# eled01.net
KiCad netlist of a schematic drawn in EAGLE
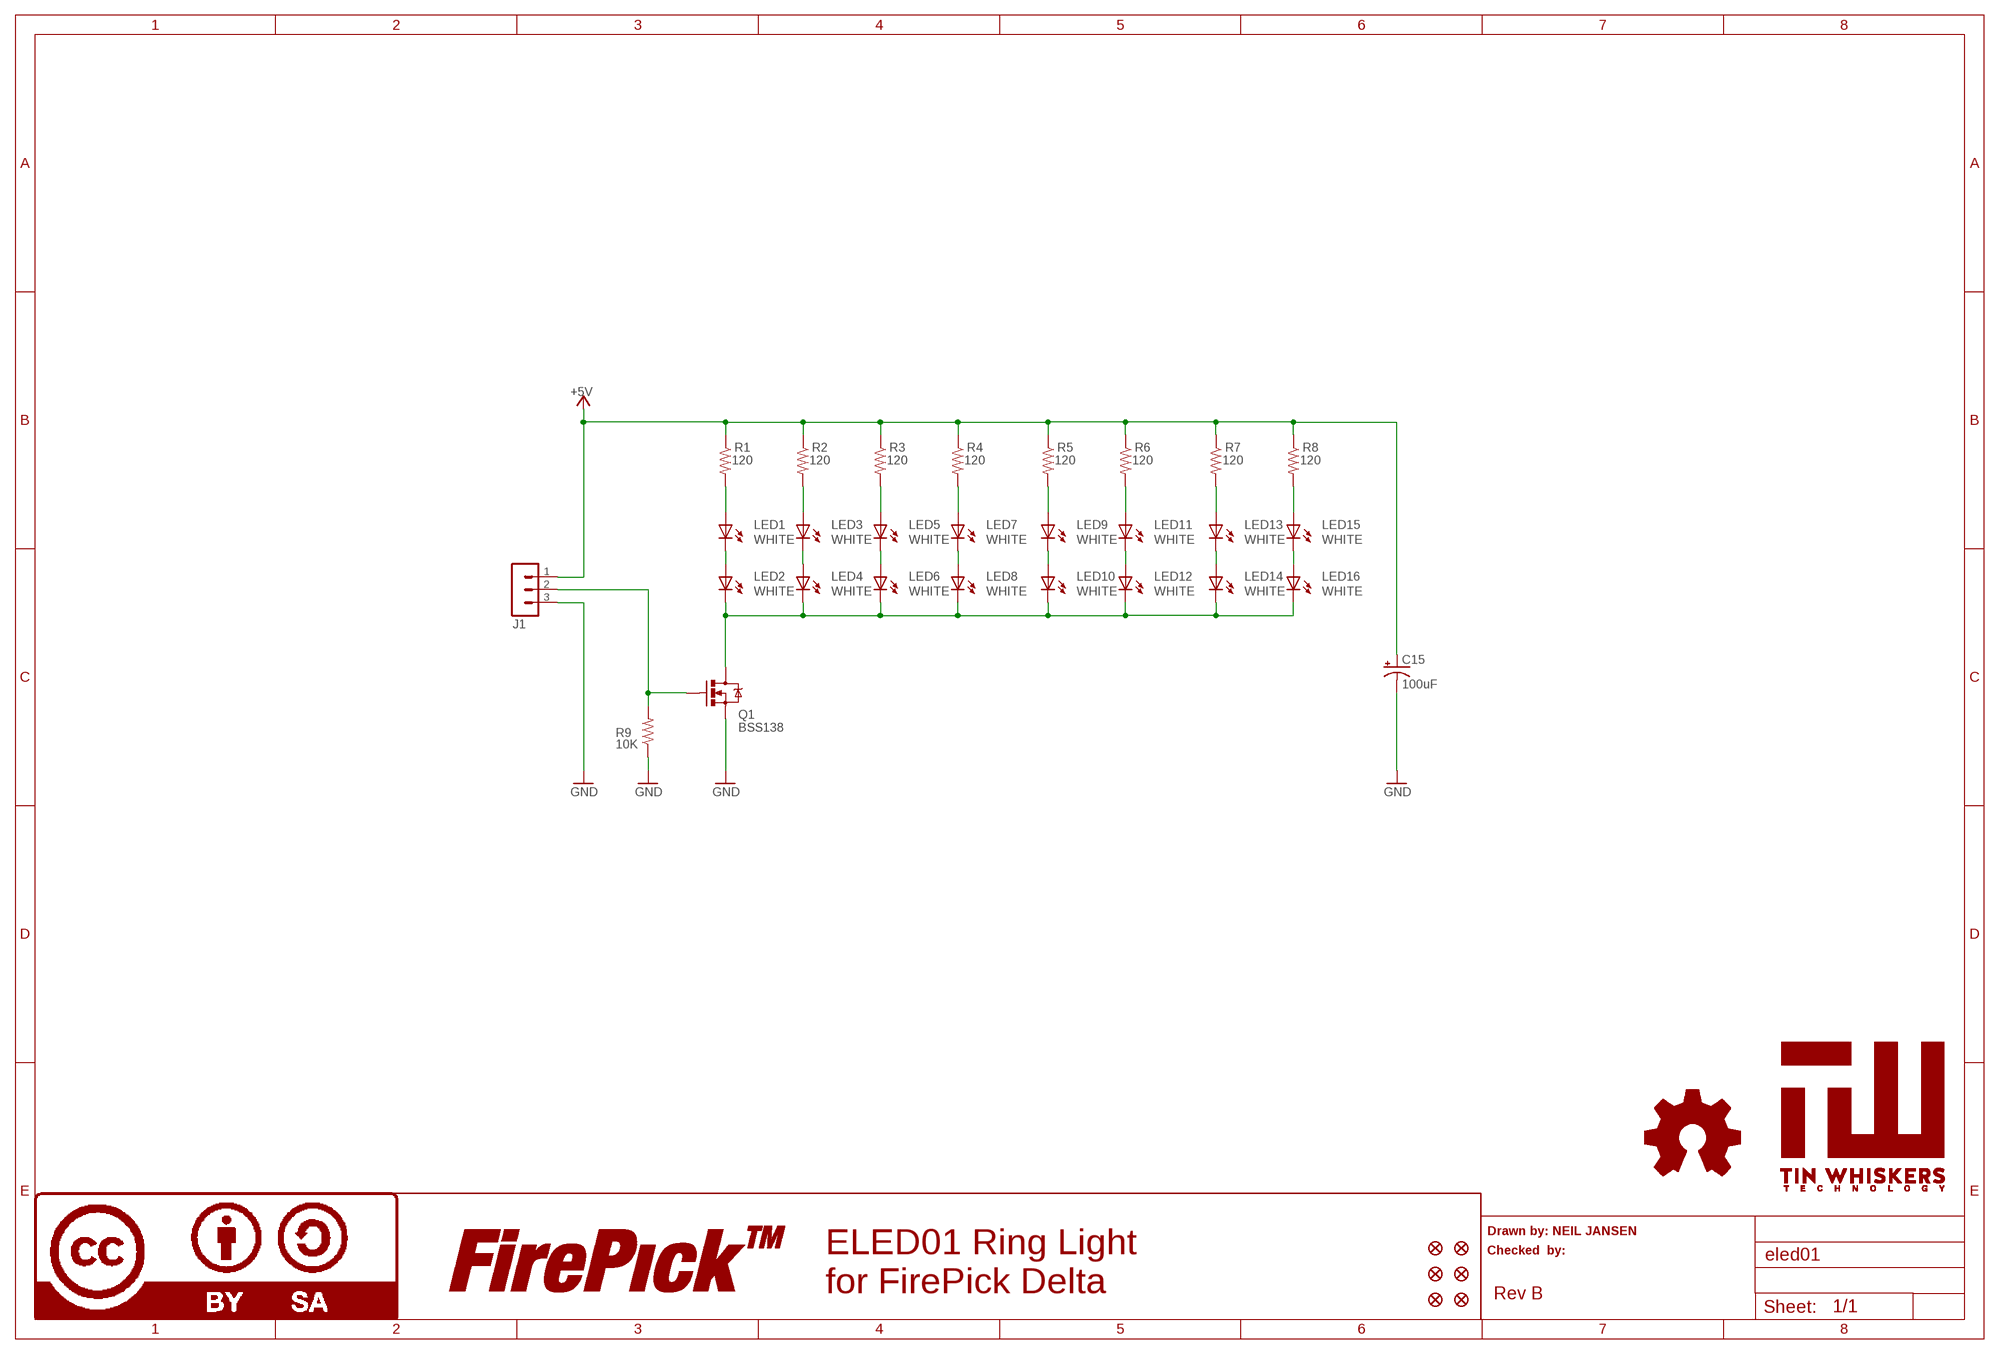
[diagram p0: schematic, sheet 1]

(export (version "E")
  (design (tool "Eeschema 10.0.6"))
  (components
    (comp (ref "C15")
      (value "100uF")
      (footprint "eagle-import:PANASONIC_D")
      (fields (field (name "PARTNO") "25TXV100M6.3X8"))
      (libsource (lib "eagle-import") (part "CPOL-USD"))
    )
    (comp (ref "FID1")
      (value "FIDUCIAL")
      (footprint "eagle-import:FIDUCIAL")
      (libsource (lib "eagle-import") (part "FIDUCIAL"))
    )
    (comp (ref "FID2")
      (value "FIDUCIAL")
      (footprint "eagle-import:FIDUCIAL")
      (libsource (lib "eagle-import") (part "FIDUCIAL"))
    )
    (comp (ref "FID3")
      (value "FIDUCIAL")
      (footprint "eagle-import:FIDUCIAL")
      (libsource (lib "eagle-import") (part "FIDUCIAL"))
    )
    (comp (ref "FID4")
      (value "FIDUCIAL")
      (footprint "eagle-import:FIDUCIAL")
      (libsource (lib "eagle-import") (part "FIDUCIAL"))
    )
    (comp (ref "FID5")
      (value "FIDUCIAL")
      (footprint "eagle-import:FIDUCIAL")
      (libsource (lib "eagle-import") (part "FIDUCIAL"))
    )
    (comp (ref "FID6")
      (value "FIDUCIAL")
      (footprint "eagle-import:FIDUCIAL")
      (libsource (lib "eagle-import") (part "FIDUCIAL"))
    )
    (comp (ref "J1")
      (value "MA03-1")
      (footprint "eagle-import:MA03-1")
      (fields (field (name "PARTNO") "CONN-0.1-RA-1X3"))
      (libsource (lib "eagle-import") (part "MA03-1"))
    )
    (comp (ref "LED1")
      (value "WHITE")
      (footprint "eagle-import:LED-1206-NO_SILK")
      (fields (field (name "PARTNO") "LTST-C150CKT"))
      (libsource (lib "eagle-import") (part "LED1206-NS"))
    )
    (comp (ref "LED2")
      (value "WHITE")
      (footprint "eagle-import:LED-1206-NO_SILK")
      (fields (field (name "PARTNO") "LTST-C150CKT"))
      (libsource (lib "eagle-import") (part "LED1206-NS"))
    )
    (comp (ref "LED3")
      (value "WHITE")
      (footprint "eagle-import:LED-1206-NO_SILK")
      (fields (field (name "PARTNO") "LTST-C150CKT"))
      (libsource (lib "eagle-import") (part "LED1206-NS"))
    )
    (comp (ref "LED4")
      (value "WHITE")
      (footprint "eagle-import:LED-1206-NO_SILK")
      (fields (field (name "PARTNO") "LTST-C150CKT"))
      (libsource (lib "eagle-import") (part "LED1206-NS"))
    )
    (comp (ref "LED5")
      (value "WHITE")
      (footprint "eagle-import:LED-1206-NO_SILK")
      (fields (field (name "PARTNO") "LTST-C150CKT"))
      (libsource (lib "eagle-import") (part "LED1206-NS"))
    )
    (comp (ref "LED6")
      (value "WHITE")
      (footprint "eagle-import:LED-1206-NO_SILK")
      (fields (field (name "PARTNO") "LTST-C150CKT"))
      (libsource (lib "eagle-import") (part "LED1206-NS"))
    )
    (comp (ref "LED7")
      (value "WHITE")
      (footprint "eagle-import:LED-1206-NO_SILK")
      (fields (field (name "PARTNO") "LTST-C150CKT"))
      (libsource (lib "eagle-import") (part "LED1206-NS"))
    )
    (comp (ref "LED8")
      (value "WHITE")
      (footprint "eagle-import:LED-1206-NO_SILK")
      (fields (field (name "PARTNO") "LTST-C150CKT"))
      (libsource (lib "eagle-import") (part "LED1206-NS"))
    )
    (comp (ref "LED9")
      (value "WHITE")
      (footprint "eagle-import:LED-1206-NO_SILK")
      (fields (field (name "PARTNO") "LTST-C150CKT"))
      (libsource (lib "eagle-import") (part "LED1206-NS"))
    )
    (comp (ref "LED10")
      (value "WHITE")
      (footprint "eagle-import:LED-1206-NO_SILK")
      (fields (field (name "PARTNO") "LTST-C150CKT"))
      (libsource (lib "eagle-import") (part "LED1206-NS"))
    )
    (comp (ref "LED11")
      (value "WHITE")
      (footprint "eagle-import:LED-1206-NO_SILK")
      (fields (field (name "PARTNO") "LTST-C150CKT"))
      (libsource (lib "eagle-import") (part "LED1206-NS"))
    )
    (comp (ref "LED12")
      (value "WHITE")
      (footprint "eagle-import:LED-1206-NO_SILK")
      (fields (field (name "PARTNO") "LTST-C150CKT"))
      (libsource (lib "eagle-import") (part "LED1206-NS"))
    )
    (comp (ref "LED13")
      (value "WHITE")
      (footprint "eagle-import:LED-1206-NO_SILK")
      (fields (field (name "PARTNO") "LTST-C150CKT"))
      (libsource (lib "eagle-import") (part "LED1206-NS"))
    )
    (comp (ref "LED14")
      (value "WHITE")
      (footprint "eagle-import:LED-1206-NO_SILK")
      (fields (field (name "PARTNO") "LTST-C150CKT"))
      (libsource (lib "eagle-import") (part "LED1206-NS"))
    )
    (comp (ref "LED15")
      (value "WHITE")
      (footprint "eagle-import:LED-1206-NO_SILK")
      (fields (field (name "PARTNO") "LTST-C150CKT"))
      (libsource (lib "eagle-import") (part "LED1206-NS"))
    )
    (comp (ref "LED16")
      (value "WHITE")
      (footprint "eagle-import:LED-1206-NO_SILK")
      (fields (field (name "PARTNO") "LTST-C150CKT"))
      (libsource (lib "eagle-import") (part "LED1206-NS"))
    )
    (comp (ref "LOGO2")
      (value "LOGO-OSHWSMALL")
      (footprint "eagle-import:LOGO-OSHW-SMALL")
      (libsource (lib "eagle-import") (part "LOGO-OSHWSMALL"))
    )
    (comp (ref "LOGO4")
      (value "LOGO-FIREPICKMEDIUM")
      (footprint "eagle-import:LOGO-FIREPICK-MEDIUM")
      (libsource (lib "eagle-import") (part "LOGO-FIREPICKMEDIUM"))
    )
    (comp (ref "LOGO6")
      (value "LOGO-CC-BY-SAMEDIUM")
      (footprint "eagle-import:LOGO-CC-BY-SA-MEDIUM")
      (libsource (lib "eagle-import") (part "LOGO-CC-BY-SAMEDIUM"))
    )
    (comp (ref "Q1")
      (value "BSS138")
      (footprint "eagle-import:SOT23")
      (libsource (lib "eagle-import") (part "MOSFET-NCHANNELBSS138"))
    )
    (comp (ref "R1")
      (value "120")
      (footprint "eagle-import:0805")
      (fields (field (name "PARTNO") "RC0805FR-07120RL"))
      (libsource (lib "eagle-import") (part "RESISTOR0805-RES"))
    )
    (comp (ref "R2")
      (value "120")
      (footprint "eagle-import:0805")
      (fields (field (name "PARTNO") "RC0805FR-07120RL"))
      (libsource (lib "eagle-import") (part "RESISTOR0805-RES"))
    )
    (comp (ref "R3")
      (value "120")
      (footprint "eagle-import:0805")
      (fields (field (name "PARTNO") "RC0805FR-07120RL"))
      (libsource (lib "eagle-import") (part "RESISTOR0805-RES"))
    )
    (comp (ref "R4")
      (value "120")
      (footprint "eagle-import:0805")
      (fields (field (name "PARTNO") "RC0805FR-07120RL"))
      (libsource (lib "eagle-import") (part "RESISTOR0805-RES"))
    )
    (comp (ref "R5")
      (value "120")
      (footprint "eagle-import:0805")
      (fields (field (name "PARTNO") "RC0805FR-07120RL"))
      (libsource (lib "eagle-import") (part "RESISTOR0805-RES"))
    )
    (comp (ref "R6")
      (value "120")
      (footprint "eagle-import:0805")
      (fields (field (name "PARTNO") "RC0805FR-07120RL"))
      (libsource (lib "eagle-import") (part "RESISTOR0805-RES"))
    )
    (comp (ref "R7")
      (value "120")
      (footprint "eagle-import:0805")
      (fields (field (name "PARTNO") "RC0805FR-07120RL"))
      (libsource (lib "eagle-import") (part "RESISTOR0805-RES"))
    )
    (comp (ref "R8")
      (value "120")
      (footprint "eagle-import:0805")
      (fields (field (name "PARTNO") "RC0805FR-07120RL"))
      (libsource (lib "eagle-import") (part "RESISTOR0805-RES"))
    )
    (comp (ref "R9")
      (value "10K")
      (footprint "eagle-import:0805")
      (fields (field (name "PARTNO") "RC0805FR-0710KL"))
      (libsource (lib "eagle-import") (part "RESISTOR0805-RES"))
    )
    (comp (ref "U$1")
      (value "TIN-WHISKERSSMALL")
      (footprint "eagle-import:TIN-WHISKERS-SMALL")
      (libsource (lib "eagle-import") (part "TIN-WHISKERSSMALL"))
    )
  )
  (nets
    (net (code "1") (name "+5V") (class "Default")
      (node (ref "C15") (pin "+") (pinfunction "+_+") (pintype "passive"))
      (node (ref "J1") (pin "1") (pinfunction "1_1") (pintype "passive"))
      (node (ref "R1") (pin "1") (pinfunction "1_1") (pintype "passive"))
      (node (ref "R2") (pin "1") (pinfunction "1_1") (pintype "passive"))
      (node (ref "R3") (pin "1") (pinfunction "1_1") (pintype "passive"))
      (node (ref "R4") (pin "1") (pinfunction "1_1") (pintype "passive"))
      (node (ref "R5") (pin "1") (pinfunction "1_1") (pintype "passive"))
      (node (ref "R6") (pin "1") (pinfunction "1_1") (pintype "passive"))
      (node (ref "R7") (pin "1") (pinfunction "1_1") (pintype "passive"))
      (node (ref "R8") (pin "1") (pinfunction "1_1") (pintype "passive"))
    )
    (net (code "2") (name "GND") (class "Default")
      (node (ref "C15") (pin "-") (pinfunction "-_-") (pintype "passive"))
      (node (ref "J1") (pin "3") (pinfunction "3_3") (pintype "passive"))
      (node (ref "Q1") (pin "2") (pinfunction "S_2") (pintype "passive"))
      (node (ref "R9") (pin "1") (pinfunction "1_1") (pintype "passive"))
    )
    (net (code "3") (name "Net-(LED1-PadA)") (class "Default")
      (node (ref "LED1") (pin "A") (pinfunction "A_A") (pintype "passive"))
      (node (ref "R1") (pin "2") (pinfunction "2_2") (pintype "passive"))
    )
    (net (code "4") (name "Net-(LED1-PadC)") (class "Default")
      (node (ref "LED1") (pin "C") (pinfunction "C_C") (pintype "passive"))
      (node (ref "LED2") (pin "A") (pinfunction "A_A") (pintype "passive"))
    )
    (net (code "5") (name "Net-(LED3-PadA)") (class "Default")
      (node (ref "LED3") (pin "A") (pinfunction "A_A") (pintype "passive"))
      (node (ref "R2") (pin "2") (pinfunction "2_2") (pintype "passive"))
    )
    (net (code "6") (name "Net-(LED3-PadC)") (class "Default")
      (node (ref "LED3") (pin "C") (pinfunction "C_C") (pintype "passive"))
      (node (ref "LED4") (pin "A") (pinfunction "A_A") (pintype "passive"))
    )
    (net (code "7") (name "Net-(LED5-PadA)") (class "Default")
      (node (ref "LED5") (pin "A") (pinfunction "A_A") (pintype "passive"))
      (node (ref "R3") (pin "2") (pinfunction "2_2") (pintype "passive"))
    )
    (net (code "8") (name "Net-(LED5-PadC)") (class "Default")
      (node (ref "LED5") (pin "C") (pinfunction "C_C") (pintype "passive"))
      (node (ref "LED6") (pin "A") (pinfunction "A_A") (pintype "passive"))
    )
    (net (code "9") (name "Net-(LED7-PadA)") (class "Default")
      (node (ref "LED7") (pin "A") (pinfunction "A_A") (pintype "passive"))
      (node (ref "R4") (pin "2") (pinfunction "2_2") (pintype "passive"))
    )
    (net (code "10") (name "Net-(LED7-PadC)") (class "Default")
      (node (ref "LED7") (pin "C") (pinfunction "C_C") (pintype "passive"))
      (node (ref "LED8") (pin "A") (pinfunction "A_A") (pintype "passive"))
    )
    (net (code "11") (name "Net-(LED9-PadA)") (class "Default")
      (node (ref "LED9") (pin "A") (pinfunction "A_A") (pintype "passive"))
      (node (ref "R5") (pin "2") (pinfunction "2_2") (pintype "passive"))
    )
    (net (code "12") (name "Net-(LED10-PadA)") (class "Default")
      (node (ref "LED10") (pin "A") (pinfunction "A_A") (pintype "passive"))
      (node (ref "LED9") (pin "C") (pinfunction "C_C") (pintype "passive"))
    )
    (net (code "13") (name "Net-(LED11-PadA)") (class "Default")
      (node (ref "LED11") (pin "A") (pinfunction "A_A") (pintype "passive"))
      (node (ref "R6") (pin "2") (pinfunction "2_2") (pintype "passive"))
    )
    (net (code "14") (name "Net-(LED11-PadC)") (class "Default")
      (node (ref "LED11") (pin "C") (pinfunction "C_C") (pintype "passive"))
      (node (ref "LED12") (pin "A") (pinfunction "A_A") (pintype "passive"))
    )
    (net (code "15") (name "Net-(LED13-PadA)") (class "Default")
      (node (ref "LED13") (pin "A") (pinfunction "A_A") (pintype "passive"))
      (node (ref "R7") (pin "2") (pinfunction "2_2") (pintype "passive"))
    )
    (net (code "16") (name "Net-(LED13-PadC)") (class "Default")
      (node (ref "LED13") (pin "C") (pinfunction "C_C") (pintype "passive"))
      (node (ref "LED14") (pin "A") (pinfunction "A_A") (pintype "passive"))
    )
    (net (code "17") (name "Net-(LED15-PadA)") (class "Default")
      (node (ref "LED15") (pin "A") (pinfunction "A_A") (pintype "passive"))
      (node (ref "R8") (pin "2") (pinfunction "2_2") (pintype "passive"))
    )
    (net (code "18") (name "Net-(LED15-PadC)") (class "Default")
      (node (ref "LED15") (pin "C") (pinfunction "C_C") (pintype "passive"))
      (node (ref "LED16") (pin "A") (pinfunction "A_A") (pintype "passive"))
    )
    (net (code "19") (name "Net-(Q1-D)") (class "Default")
      (node (ref "LED10") (pin "C") (pinfunction "C_C") (pintype "passive"))
      (node (ref "LED12") (pin "C") (pinfunction "C_C") (pintype "passive"))
      (node (ref "LED14") (pin "C") (pinfunction "C_C") (pintype "passive"))
      (node (ref "LED16") (pin "C") (pinfunction "C_C") (pintype "passive"))
      (node (ref "LED2") (pin "C") (pinfunction "C_C") (pintype "passive"))
      (node (ref "LED4") (pin "C") (pinfunction "C_C") (pintype "passive"))
      (node (ref "LED6") (pin "C") (pinfunction "C_C") (pintype "passive"))
      (node (ref "LED8") (pin "C") (pinfunction "C_C") (pintype "passive"))
      (node (ref "Q1") (pin "3") (pinfunction "D_3") (pintype "passive"))
    )
    (net (code "20") (name "Net-(Q1-G)") (class "Default")
      (node (ref "J1") (pin "2") (pinfunction "2_2") (pintype "passive"))
      (node (ref "Q1") (pin "1") (pinfunction "G_1") (pintype "passive"))
      (node (ref "R9") (pin "2") (pinfunction "2_2") (pintype "passive"))
    )
  )
)
